# MRIRspBox20220129.net
KiCad netlist of a schematic drawn in EAGLE
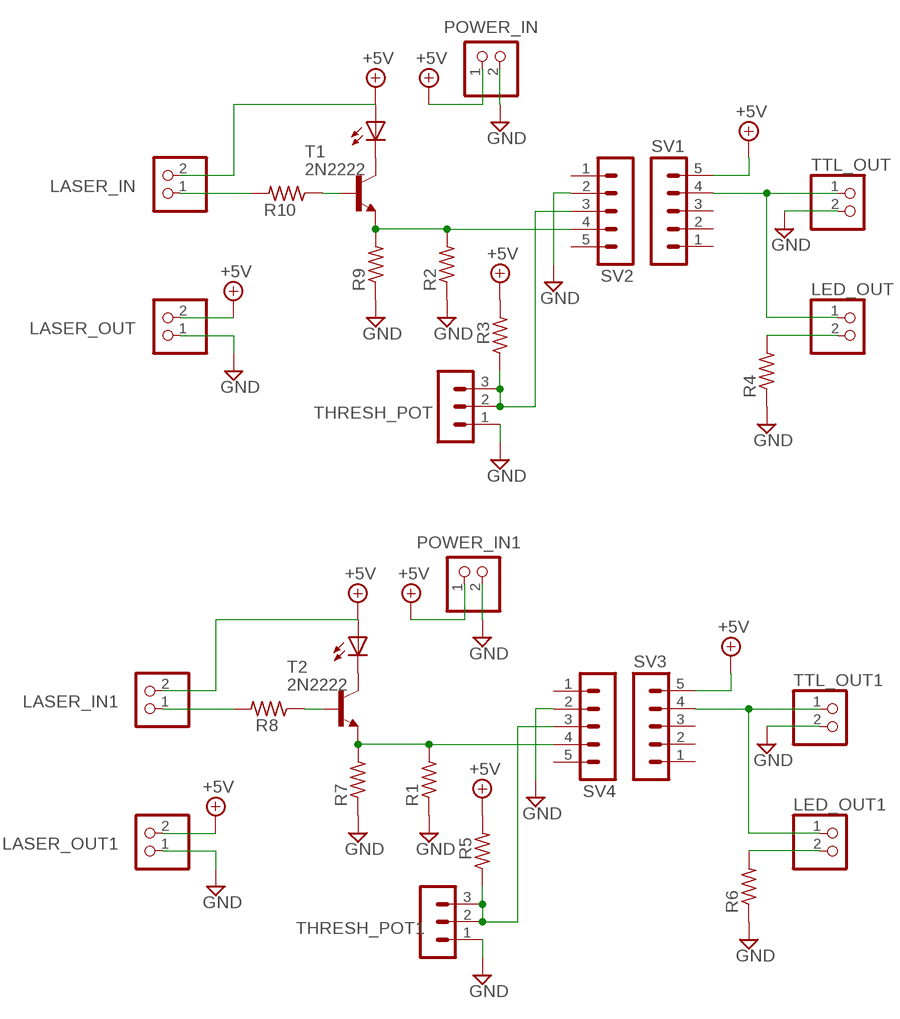
[diagram p0: schematic, sheet 1]

(export (version "E")
  (design (tool "Eeschema 10.0.6"))
  (components
    (comp (ref "LASER_IN")
      (value "PINHD-1X2")
      (footprint "eagle-import:1X02")
      (libsource (lib "eagle-import") (part "PINHD-1X2"))
    )
    (comp (ref "LASER_IN1")
      (value "PINHD-1X2")
      (footprint "eagle-import:1X02")
      (libsource (lib "eagle-import") (part "PINHD-1X2"))
    )
    (comp (ref "LASER_OUT")
      (value "PINHD-1X2")
      (footprint "eagle-import:1X02")
      (libsource (lib "eagle-import") (part "PINHD-1X2"))
    )
    (comp (ref "LASER_OUT1")
      (value "PINHD-1X2")
      (footprint "eagle-import:1X02")
      (libsource (lib "eagle-import") (part "PINHD-1X2"))
    )
    (comp (ref "LED1")
      (value "LED_ELD260")
      (footprint "eagle-import:LED_LD260")
      (libsource (lib "eagle-import") (part "LED_ELD260"))
    )
    (comp (ref "LED2")
      (value "LED_ELD260")
      (footprint "eagle-import:LED_LD260")
      (libsource (lib "eagle-import") (part "LED_ELD260"))
    )
    (comp (ref "LED_OUT")
      (value "PINHD-1X2")
      (footprint "eagle-import:1X02")
      (libsource (lib "eagle-import") (part "PINHD-1X2"))
    )
    (comp (ref "LED_OUT1")
      (value "PINHD-1X2")
      (footprint "eagle-import:1X02")
      (libsource (lib "eagle-import") (part "PINHD-1X2"))
    )
    (comp (ref "POWER_IN")
      (value "PINHD-1X2")
      (footprint "eagle-import:1X02")
      (libsource (lib "eagle-import") (part "PINHD-1X2"))
    )
    (comp (ref "POWER_IN1")
      (value "PINHD-1X2")
      (footprint "eagle-import:1X02")
      (libsource (lib "eagle-import") (part "PINHD-1X2"))
    )
    (comp (ref "R1")
      (value "R-US_0207/12")
      (footprint "eagle-import:0207_12")
      (libsource (lib "eagle-import") (part "R-US_0207/12"))
    )
    (comp (ref "R2")
      (value "R-US_0207/12")
      (footprint "eagle-import:0207_12")
      (libsource (lib "eagle-import") (part "R-US_0207/12"))
    )
    (comp (ref "R3")
      (value "R-US_0207/12")
      (footprint "eagle-import:0207_12")
      (libsource (lib "eagle-import") (part "R-US_0207/12"))
    )
    (comp (ref "R4")
      (value "R-US_0207/12")
      (footprint "eagle-import:0207_12")
      (libsource (lib "eagle-import") (part "R-US_0207/12"))
    )
    (comp (ref "R5")
      (value "R-US_0207/12")
      (footprint "eagle-import:0207_12")
      (libsource (lib "eagle-import") (part "R-US_0207/12"))
    )
    (comp (ref "R6")
      (value "R-US_0207/12")
      (footprint "eagle-import:0207_12")
      (libsource (lib "eagle-import") (part "R-US_0207/12"))
    )
    (comp (ref "R7")
      (value "R-US_0207/12")
      (footprint "eagle-import:0207_12")
      (libsource (lib "eagle-import") (part "R-US_0207/12"))
    )
    (comp (ref "R8")
      (value "R-US_0207/12")
      (footprint "eagle-import:0207_12")
      (libsource (lib "eagle-import") (part "R-US_0207/12"))
    )
    (comp (ref "R9")
      (value "R-US_0207/12")
      (footprint "eagle-import:0207_12")
      (libsource (lib "eagle-import") (part "R-US_0207/12"))
    )
    (comp (ref "R10")
      (value "R-US_0207/12")
      (footprint "eagle-import:0207_12")
      (libsource (lib "eagle-import") (part "R-US_0207/12"))
    )
    (comp (ref "SV1")
      (value "MA05-1")
      (footprint "eagle-import:MA05-1")
      (libsource (lib "eagle-import") (part "MA05-1"))
    )
    (comp (ref "SV2")
      (value "MA05-1")
      (footprint "eagle-import:MA05-1")
      (libsource (lib "eagle-import") (part "MA05-1"))
    )
    (comp (ref "SV3")
      (value "MA05-1")
      (footprint "eagle-import:MA05-1")
      (libsource (lib "eagle-import") (part "MA05-1"))
    )
    (comp (ref "SV4")
      (value "MA05-1")
      (footprint "eagle-import:MA05-1")
      (libsource (lib "eagle-import") (part "MA05-1"))
    )
    (comp (ref "T1")
      (value "2N2222")
      (footprint "eagle-import:TO92-EBC-OVAL")
      (libsource (lib "eagle-import") (part "2N2222"))
    )
    (comp (ref "T2")
      (value "2N2222")
      (footprint "eagle-import:TO92-EBC-OVAL")
      (libsource (lib "eagle-import") (part "2N2222"))
    )
    (comp (ref "THRESH_POT")
      (value "MA03-1")
      (footprint "eagle-import:MA03-1")
      (libsource (lib "eagle-import") (part "MA03-1"))
    )
    (comp (ref "THRESH_POT1")
      (value "MA03-1")
      (footprint "eagle-import:MA03-1")
      (libsource (lib "eagle-import") (part "MA03-1"))
    )
    (comp (ref "TTL_OUT")
      (value "PINHD-1X2")
      (footprint "eagle-import:1X02")
      (libsource (lib "eagle-import") (part "PINHD-1X2"))
    )
    (comp (ref "TTL_OUT1")
      (value "PINHD-1X2")
      (footprint "eagle-import:1X02")
      (libsource (lib "eagle-import") (part "PINHD-1X2"))
    )
  )
  (nets
    (net (code "1") (name "+5V") (class "Default")
      (node (ref "LASER_IN") (pin "2") (pinfunction "2_2") (pintype "passive"))
      (node (ref "LASER_IN1") (pin "2") (pinfunction "2_2") (pintype "passive"))
      (node (ref "LASER_OUT") (pin "2") (pinfunction "2_2") (pintype "passive"))
      (node (ref "LASER_OUT1") (pin "2") (pinfunction "2_2") (pintype "passive"))
      (node (ref "LED1") (pin "A") (pinfunction "A_A") (pintype "passive"))
      (node (ref "LED2") (pin "A") (pinfunction "A_A") (pintype "passive"))
      (node (ref "POWER_IN") (pin "1") (pinfunction "1_1") (pintype "passive"))
      (node (ref "POWER_IN1") (pin "1") (pinfunction "1_1") (pintype "passive"))
      (node (ref "R3") (pin "2") (pinfunction "2_2") (pintype "passive"))
      (node (ref "R5") (pin "2") (pinfunction "2_2") (pintype "passive"))
      (node (ref "SV1") (pin "5") (pinfunction "5_5") (pintype "passive"))
      (node (ref "SV3") (pin "5") (pinfunction "5_5") (pintype "passive"))
    )
    (net (code "2") (name "GND") (class "Default")
      (node (ref "LASER_OUT") (pin "1") (pinfunction "1_1") (pintype "passive"))
      (node (ref "LASER_OUT1") (pin "1") (pinfunction "1_1") (pintype "passive"))
      (node (ref "POWER_IN") (pin "2") (pinfunction "2_2") (pintype "passive"))
      (node (ref "POWER_IN1") (pin "2") (pinfunction "2_2") (pintype "passive"))
      (node (ref "R1") (pin "1") (pinfunction "1_1") (pintype "passive"))
      (node (ref "R2") (pin "1") (pinfunction "1_1") (pintype "passive"))
      (node (ref "R4") (pin "1") (pinfunction "1_1") (pintype "passive"))
      (node (ref "R6") (pin "1") (pinfunction "1_1") (pintype "passive"))
      (node (ref "R7") (pin "1") (pinfunction "1_1") (pintype "passive"))
      (node (ref "R9") (pin "1") (pinfunction "1_1") (pintype "passive"))
      (node (ref "SV2") (pin "2") (pinfunction "2_2") (pintype "passive"))
      (node (ref "SV4") (pin "2") (pinfunction "2_2") (pintype "passive"))
      (node (ref "THRESH_POT") (pin "1") (pinfunction "1_1") (pintype "passive"))
      (node (ref "THRESH_POT1") (pin "1") (pinfunction "1_1") (pintype "passive"))
      (node (ref "TTL_OUT") (pin "2") (pinfunction "2_2") (pintype "passive"))
      (node (ref "TTL_OUT1") (pin "2") (pinfunction "2_2") (pintype "passive"))
    )
    (net (code "3") (name "Net-(LASER_IN-Pad1)") (class "Default")
      (node (ref "LASER_IN") (pin "1") (pinfunction "1_1") (pintype "passive"))
      (node (ref "R10") (pin "2") (pinfunction "2_2") (pintype "passive"))
    )
    (net (code "4") (name "Net-(LASER_IN1-Pad1)") (class "Default")
      (node (ref "LASER_IN1") (pin "1") (pinfunction "1_1") (pintype "passive"))
      (node (ref "R8") (pin "2") (pinfunction "2_2") (pintype "passive"))
    )
    (net (code "5") (name "Net-(LED1-C)") (class "Default")
      (node (ref "LED1") (pin "K") (pinfunction "C_K") (pintype "passive"))
      (node (ref "T1") (pin "C") (pinfunction "C_C") (pintype "passive"))
    )
    (net (code "6") (name "Net-(LED2-C)") (class "Default")
      (node (ref "LED2") (pin "K") (pinfunction "C_K") (pintype "passive"))
      (node (ref "T2") (pin "C") (pinfunction "C_C") (pintype "passive"))
    )
    (net (code "7") (name "Net-(LED_OUT-Pad1)") (class "Default")
      (node (ref "LED_OUT") (pin "1") (pinfunction "1_1") (pintype "passive"))
      (node (ref "SV1") (pin "4") (pinfunction "4_4") (pintype "passive"))
      (node (ref "TTL_OUT") (pin "1") (pinfunction "1_1") (pintype "passive"))
    )
    (net (code "8") (name "Net-(LED_OUT-Pad2)") (class "Default")
      (node (ref "LED_OUT") (pin "2") (pinfunction "2_2") (pintype "passive"))
      (node (ref "R4") (pin "2") (pinfunction "2_2") (pintype "passive"))
    )
    (net (code "9") (name "Net-(LED_OUT1-Pad1)") (class "Default")
      (node (ref "LED_OUT1") (pin "1") (pinfunction "1_1") (pintype "passive"))
      (node (ref "SV3") (pin "4") (pinfunction "4_4") (pintype "passive"))
      (node (ref "TTL_OUT1") (pin "1") (pinfunction "1_1") (pintype "passive"))
    )
    (net (code "10") (name "Net-(LED_OUT1-Pad2)") (class "Default")
      (node (ref "LED_OUT1") (pin "2") (pinfunction "2_2") (pintype "passive"))
      (node (ref "R6") (pin "2") (pinfunction "2_2") (pintype "passive"))
    )
    (net (code "11") (name "Net-(R1-Pad2)") (class "Default")
      (node (ref "R1") (pin "2") (pinfunction "2_2") (pintype "passive"))
      (node (ref "R7") (pin "2") (pinfunction "2_2") (pintype "passive"))
      (node (ref "SV4") (pin "4") (pinfunction "4_4") (pintype "passive"))
      (node (ref "T2") (pin "E") (pinfunction "E_E") (pintype "passive"))
    )
    (net (code "12") (name "Net-(R2-Pad2)") (class "Default")
      (node (ref "R2") (pin "2") (pinfunction "2_2") (pintype "passive"))
      (node (ref "R9") (pin "2") (pinfunction "2_2") (pintype "passive"))
      (node (ref "SV2") (pin "4") (pinfunction "4_4") (pintype "passive"))
      (node (ref "T1") (pin "E") (pinfunction "E_E") (pintype "passive"))
    )
    (net (code "13") (name "Net-(R3-Pad1)") (class "Default")
      (node (ref "R3") (pin "1") (pinfunction "1_1") (pintype "passive"))
      (node (ref "SV2") (pin "3") (pinfunction "3_3") (pintype "passive"))
      (node (ref "THRESH_POT") (pin "2") (pinfunction "2_2") (pintype "passive"))
      (node (ref "THRESH_POT") (pin "3") (pinfunction "3_3") (pintype "passive"))
    )
    (net (code "14") (name "Net-(R5-Pad1)") (class "Default")
      (node (ref "R5") (pin "1") (pinfunction "1_1") (pintype "passive"))
      (node (ref "SV4") (pin "3") (pinfunction "3_3") (pintype "passive"))
      (node (ref "THRESH_POT1") (pin "2") (pinfunction "2_2") (pintype "passive"))
      (node (ref "THRESH_POT1") (pin "3") (pinfunction "3_3") (pintype "passive"))
    )
    (net (code "15") (name "Net-(R8-Pad1)") (class "Default")
      (node (ref "R8") (pin "1") (pinfunction "1_1") (pintype "passive"))
      (node (ref "T2") (pin "B") (pinfunction "B_B") (pintype "passive"))
    )
    (net (code "16") (name "Net-(R10-Pad1)") (class "Default")
      (node (ref "R10") (pin "1") (pinfunction "1_1") (pintype "passive"))
      (node (ref "T1") (pin "B") (pinfunction "B_B") (pintype "passive"))
    )
    (net (code "17") (name "unconnected-(SV1-Pad1)") (class "Default")
      (node (ref "SV1") (pin "1") (pinfunction "1_1") (pintype "passive"))
    )
    (net (code "18") (name "unconnected-(SV1-Pad2)") (class "Default")
      (node (ref "SV1") (pin "2") (pinfunction "2_2") (pintype "passive"))
    )
    (net (code "19") (name "unconnected-(SV1-Pad3)") (class "Default")
      (node (ref "SV1") (pin "3") (pinfunction "3_3") (pintype "passive"))
    )
    (net (code "20") (name "unconnected-(SV2-Pad1)") (class "Default")
      (node (ref "SV2") (pin "1") (pinfunction "1_1") (pintype "passive"))
    )
    (net (code "21") (name "unconnected-(SV2-Pad5)") (class "Default")
      (node (ref "SV2") (pin "5") (pinfunction "5_5") (pintype "passive"))
    )
    (net (code "22") (name "unconnected-(SV3-Pad1)") (class "Default")
      (node (ref "SV3") (pin "1") (pinfunction "1_1") (pintype "passive"))
    )
    (net (code "23") (name "unconnected-(SV3-Pad2)") (class "Default")
      (node (ref "SV3") (pin "2") (pinfunction "2_2") (pintype "passive"))
    )
    (net (code "24") (name "unconnected-(SV3-Pad3)") (class "Default")
      (node (ref "SV3") (pin "3") (pinfunction "3_3") (pintype "passive"))
    )
    (net (code "25") (name "unconnected-(SV4-Pad1)") (class "Default")
      (node (ref "SV4") (pin "1") (pinfunction "1_1") (pintype "passive"))
    )
    (net (code "26") (name "unconnected-(SV4-Pad5)") (class "Default")
      (node (ref "SV4") (pin "5") (pinfunction "5_5") (pintype "passive"))
    )
  )
)
